# socket.net
KiCad netlist of a schematic drawn in EAGLE
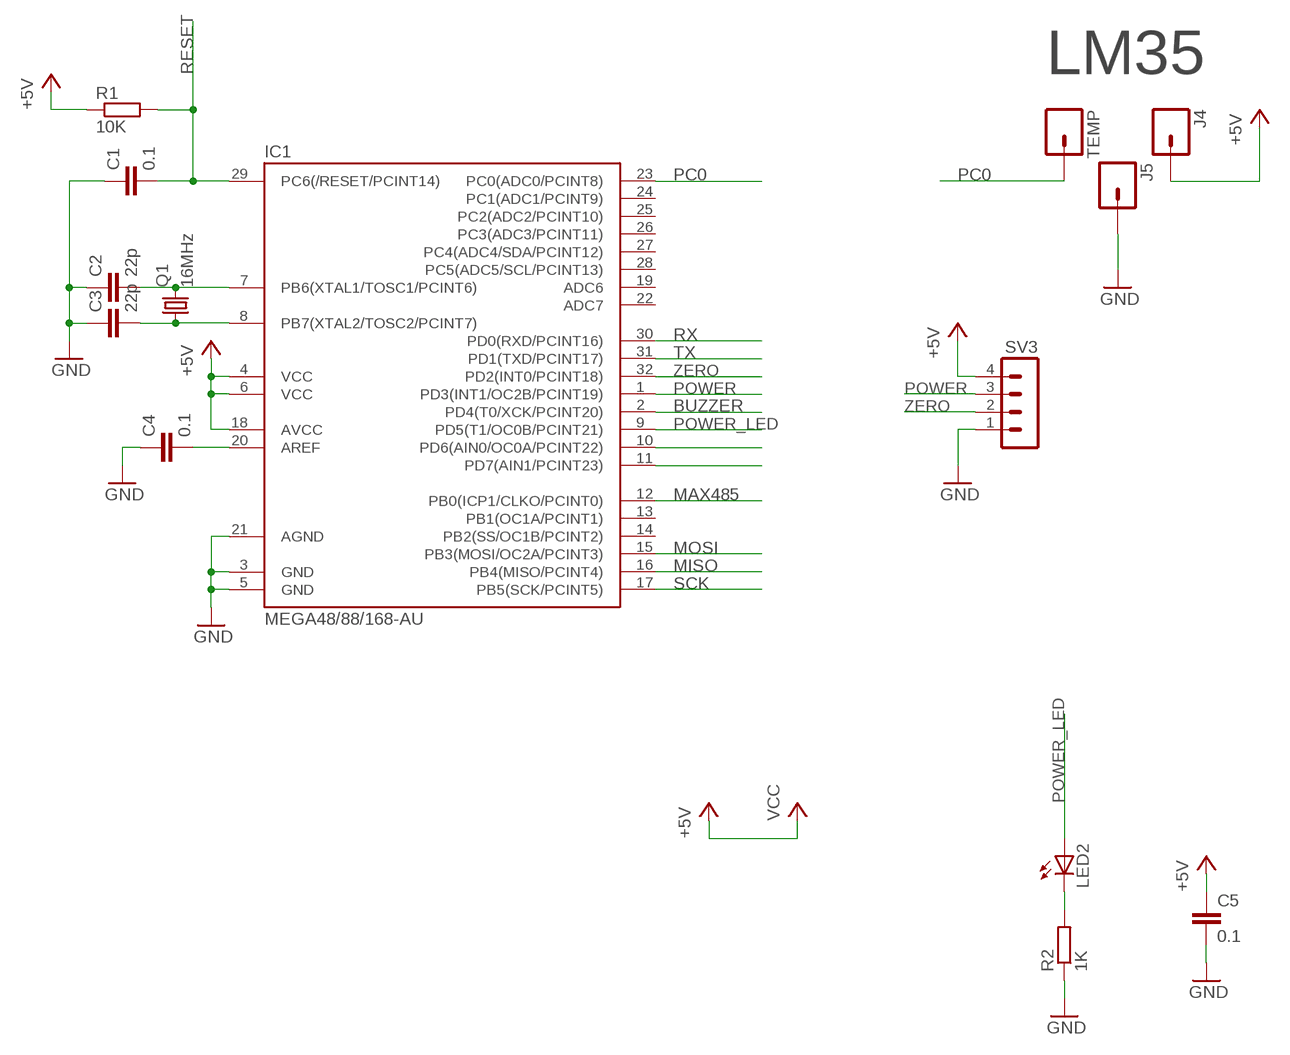
[diagram p0: schematic, sheet 1]
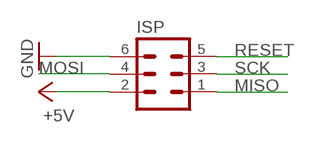
[diagram p1: schematic, sheet 2]
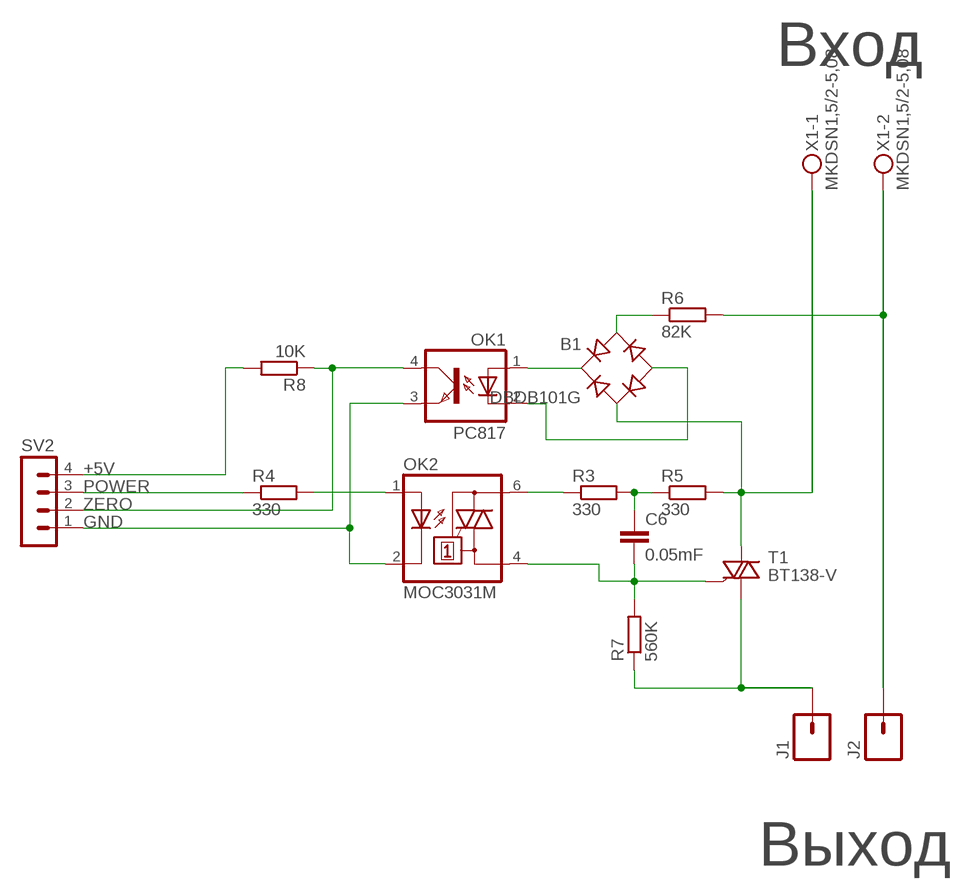
[diagram p2: schematic, sheet 3]
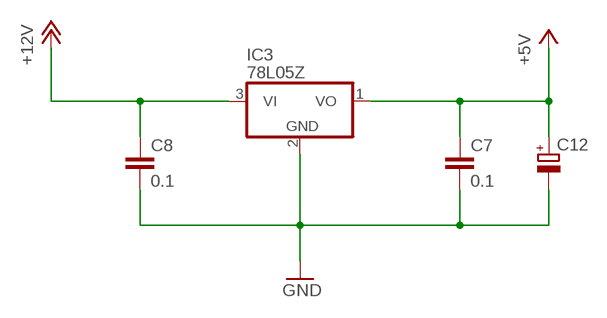
[diagram p3: schematic, sheet 4]
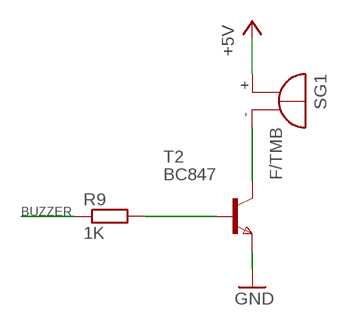
[diagram p4: schematic, sheet 5]
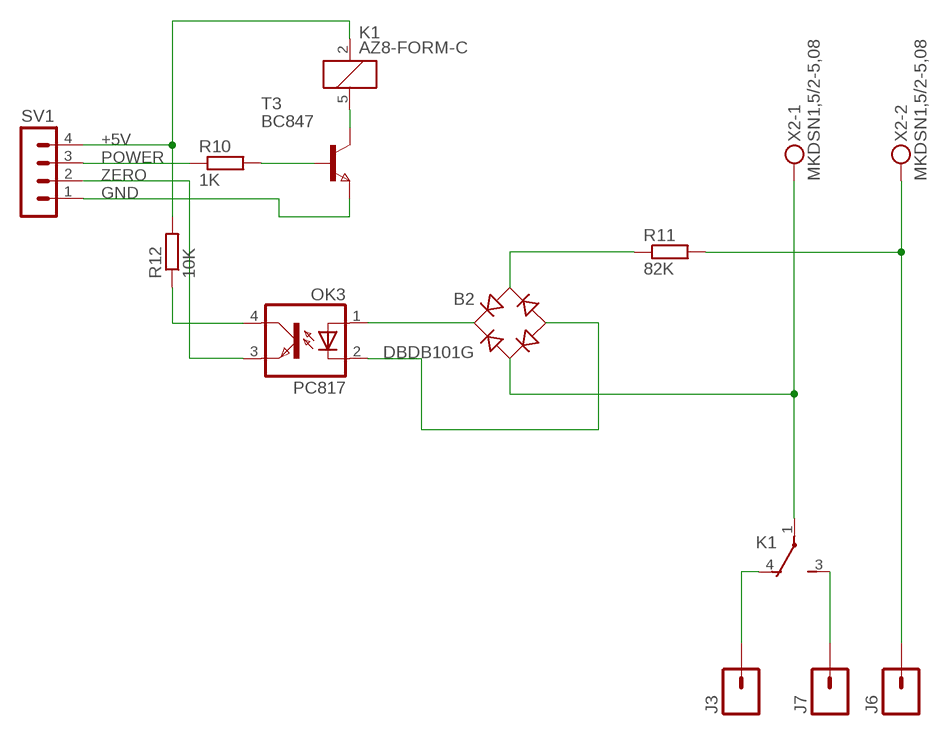
[diagram p5: schematic, sheet 6]
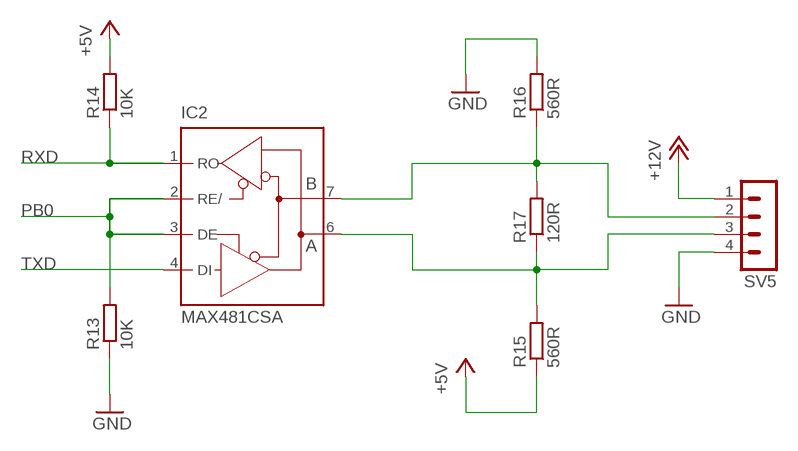
[diagram p6: schematic, sheet 7]

(export (version "E")
  (design (tool "Eeschema 10.0.6"))
  (components
    (comp (ref "B2")
      (value "DBDB101G")
      (footprint "eagle-import:DB")
      (libsource (lib "eagle-import") (part "DB?GDB101"))
    )
    (comp (ref "J3")
      (value "M01NOSILK-KIT")
      (footprint "eagle-import:1X01NS-KIT")
      (libsource (lib "eagle-import") (part "M01NOSILK-KIT"))
    )
    (comp (ref "J6")
      (value "M01NOSILK-KIT")
      (footprint "eagle-import:1X01NS-KIT")
      (libsource (lib "eagle-import") (part "M01NOSILK-KIT"))
    )
    (comp (ref "J7")
      (value "M01NOSILK-KIT")
      (footprint "eagle-import:1X01NS-KIT")
      (libsource (lib "eagle-import") (part "M01NOSILK-KIT"))
    )
    (comp (ref "K1")
      (value "AZ8-FORM-C")
      (footprint "eagle-import:AZ8")
      (libsource (lib "eagle-import") (part "AZ8-FORM-C"))
    )
    (comp (ref "OK3")
      (value "PC817")
      (footprint "eagle-import:DIL04")
      (fields (field (name "MPN") "PC817X4J000F"))
      (libsource (lib "eagle-import") (part "PC817"))
    )
    (comp (ref "R10")
      (value "1K")
      (footprint "eagle-import:M0805")
      (libsource (lib "eagle-import") (part "R-EU_M0805"))
    )
    (comp (ref "R11")
      (value "82K")
      (footprint "eagle-import:0309_10")
      (libsource (lib "eagle-import") (part "R-EU_0309/10"))
    )
    (comp (ref "R12")
      (value "10K")
      (footprint "eagle-import:M0805")
      (libsource (lib "eagle-import") (part "R-EU_M0805"))
    )
    (comp (ref "SV1")
      (value "MA04-1")
      (footprint "eagle-import:MA04-1")
      (libsource (lib "eagle-import") (part "MA04-1"))
    )
    (comp (ref "T3")
      (value "BC847")
      (footprint "eagle-import:SOT-23")
      (fields (field (name "MPN") "DSS20201L-7"))
      (libsource (lib "eagle-import") (part "NPNSOT23"))
    )
    (comp (ref "X2")
      (value "MKDSN1,5/2-5,08")
      (footprint "eagle-import:MKDSN1,5_2-5,08")
      (libsource (lib "eagle-import") (part "MKDSN1,5/2-5,08"))
    )
    (comp (ref "IC2")
      (value "MAX481CSA")
      (footprint "eagle-import:SO08")
      (fields (field (name "MF") "MAXIM"))
      (libsource (lib "eagle-import") (part "MAX481CSA"))
    )
    (comp (ref "R13")
      (value "10K")
      (footprint "eagle-import:R0805")
      (libsource (lib "eagle-import") (part "resistor_R-EU_R0805"))
    )
    (comp (ref "R14")
      (value "10K")
      (footprint "eagle-import:R0805")
      (libsource (lib "eagle-import") (part "resistor_R-EU_R0805"))
    )
    (comp (ref "R15")
      (value "560R")
      (footprint "eagle-import:R0805")
      (libsource (lib "eagle-import") (part "resistor_R-EU_R0805"))
    )
    (comp (ref "R16")
      (value "560R")
      (footprint "eagle-import:R0805")
      (libsource (lib "eagle-import") (part "resistor_R-EU_R0805"))
    )
    (comp (ref "R17")
      (value "120R")
      (footprint "eagle-import:R0805")
      (libsource (lib "eagle-import") (part "resistor_R-EU_R0805"))
    )
    (comp (ref "SV5")
      (value "MA04-1")
      (footprint "eagle-import:MA04-1")
      (libsource (lib "eagle-import") (part "MA04-1"))
    )
    (comp (ref "C7")
      (value "0.1")
      (footprint "eagle-import:C0805")
      (libsource (lib "eagle-import") (part "C-EUC0805"))
    )
    (comp (ref "C8")
      (value "0.1")
      (footprint "eagle-import:C0805")
      (libsource (lib "eagle-import") (part "C-EUC0805"))
    )
    (comp (ref "C12")
      (value "CPOL-EUE2,5-6E")
      (footprint "eagle-import:E2,5-6E")
      (libsource (lib "eagle-import") (part "CPOL-EUE2,5-6E"))
    )
    (comp (ref "IC3")
      (value "78L05Z")
      (footprint "eagle-import:TO92")
      (libsource (lib "eagle-import") (part "78ZL05"))
    )
    (comp (ref "B1")
      (value "DBDB101G")
      (footprint "eagle-import:DB")
      (libsource (lib "eagle-import") (part "DB?GDB101"))
    )
    (comp (ref "C6")
      (value "0.05mF")
      (footprint "eagle-import:C0805")
      (libsource (lib "eagle-import") (part "C-EUC0805"))
    )
    (comp (ref "J1")
      (value "M01NOSILK-KIT")
      (footprint "eagle-import:1X01NS-KIT")
      (libsource (lib "eagle-import") (part "M01NOSILK-KIT"))
    )
    (comp (ref "J2")
      (value "M01NOSILK-KIT")
      (footprint "eagle-import:1X01NS-KIT")
      (libsource (lib "eagle-import") (part "M01NOSILK-KIT"))
    )
    (comp (ref "OK1")
      (value "PC817")
      (footprint "eagle-import:DIL04")
      (fields (field (name "MPN") "PC817X4J000F"))
      (libsource (lib "eagle-import") (part "PC817"))
    )
    (comp (ref "OK2")
      (value "MOC3031M")
      (footprint "eagle-import:DIL06")
      (fields (field (name "MF") "FAIRCHILD SEMICONDUCTOR"))
      (libsource (lib "eagle-import") (part "MOC3031M"))
    )
    (comp (ref "R3")
      (value "330")
      (footprint "eagle-import:M0805")
      (libsource (lib "eagle-import") (part "R-EU_M0805"))
    )
    (comp (ref "R4")
      (value "330")
      (footprint "eagle-import:M0805")
      (libsource (lib "eagle-import") (part "R-EU_M0805"))
    )
    (comp (ref "R5")
      (value "330")
      (footprint "eagle-import:M0805")
      (libsource (lib "eagle-import") (part "R-EU_M0805"))
    )
    (comp (ref "R6")
      (value "82K")
      (footprint "eagle-import:0309_10")
      (libsource (lib "eagle-import") (part "R-EU_0309/10"))
    )
    (comp (ref "R7")
      (value "560K")
      (footprint "eagle-import:M0805")
      (libsource (lib "eagle-import") (part "R-EU_M0805"))
    )
    (comp (ref "R8")
      (value "10K")
      (footprint "eagle-import:M0805")
      (libsource (lib "eagle-import") (part "R-EU_M0805"))
    )
    (comp (ref "SV2")
      (value "MA04-1")
      (footprint "eagle-import:MA04-1")
      (libsource (lib "eagle-import") (part "MA04-1"))
    )
    (comp (ref "T1")
      (value "BT138-V")
      (footprint "eagle-import:TO220BV")
      (libsource (lib "eagle-import") (part "BT138-V"))
    )
    (comp (ref "X1")
      (value "MKDSN1,5/2-5,08")
      (footprint "eagle-import:MKDSN1,5_2-5,08")
      (libsource (lib "eagle-import") (part "MKDSN1,5/2-5,08"))
    )
    (comp (ref "C1")
      (value "0.1")
      (footprint "eagle-import:C0805")
      (libsource (lib "eagle-import") (part "C-EUC0805"))
    )
    (comp (ref "C2")
      (value "22p")
      (footprint "eagle-import:C0805")
      (libsource (lib "eagle-import") (part "C-EUC0805"))
    )
    (comp (ref "C3")
      (value "22p")
      (footprint "eagle-import:C0805")
      (libsource (lib "eagle-import") (part "C-EUC0805"))
    )
    (comp (ref "C4")
      (value "0.1")
      (footprint "eagle-import:C0805")
      (libsource (lib "eagle-import") (part "C-EUC0805"))
    )
    (comp (ref "C5")
      (value "0.1")
      (footprint "eagle-import:C0805")
      (libsource (lib "eagle-import") (part "C-EUC0805"))
    )
    (comp (ref "IC1")
      (value "MEGA48/88/168-AU")
      (footprint "eagle-import:TQFP32-08")
      (libsource (lib "eagle-import") (part "MEGA48/88/168-AU"))
    )
    (comp (ref "J4")
      (value "M01PTH_NO_SILK_YES_STOP")
      (footprint "eagle-import:1X01_NO_SILK")
      (libsource (lib "eagle-import") (part "M01PTH_NO_SILK_YES_STOP"))
    )
    (comp (ref "J5")
      (value "M01PTH_NO_SILK_YES_STOP")
      (footprint "eagle-import:1X01_NO_SILK")
      (libsource (lib "eagle-import") (part "M01PTH_NO_SILK_YES_STOP"))
    )
    (comp (ref "LED2")
      (value "LEDCHIPLED_0805")
      (footprint "eagle-import:CHIPLED_0805")
      (libsource (lib "eagle-import") (part "LEDCHIPLED_0805"))
    )
    (comp (ref "Q1")
      (value "16MHz")
      (footprint "eagle-import:HC49U70")
      (libsource (lib "eagle-import") (part "CRYSTALHC49U70"))
    )
    (comp (ref "R1")
      (value "10K")
      (footprint "eagle-import:R0805")
      (libsource (lib "eagle-import") (part "R-EU_R0805"))
    )
    (comp (ref "R2")
      (value "1K")
      (footprint "eagle-import:R0805")
      (libsource (lib "eagle-import") (part "R-EU_R0805"))
    )
    (comp (ref "SV3")
      (value "MA04-1")
      (footprint "eagle-import:MA04-1")
      (libsource (lib "eagle-import") (part "MA04-1"))
    )
    (comp (ref "TEMP")
      (value "M01PTH_NO_SILK_YES_STOP")
      (footprint "eagle-import:1X01_NO_SILK")
      (libsource (lib "eagle-import") (part "M01PTH_NO_SILK_YES_STOP"))
    )
    (comp (ref "R9")
      (value "1K")
      (footprint "eagle-import:M1206")
      (libsource (lib "eagle-import") (part "R-EU_M1206"))
    )
    (comp (ref "SG1")
      (value "F/TMB")
      (footprint "eagle-import:F_TMB")
      (libsource (lib "eagle-import") (part "F/TMB"))
    )
    (comp (ref "T2")
      (value "BC847")
      (footprint "eagle-import:SOT-23")
      (fields (field (name "MPN") "DSS20201L-7"))
      (libsource (lib "eagle-import") (part "NPNSOT23"))
    )
    (comp (ref "ISP")
      (value "MA03-2")
      (footprint "eagle-import:MA03-2")
      (libsource (lib "eagle-import") (part "MA03-2"))
    )
  )
  (nets
    (net (code "1") (name "+5V") (class "Default")
      (node (ref "C12") (pin "+") (pinfunction "+_+") (pintype "passive"))
      (node (ref "C5") (pin "1") (pinfunction "1_1") (pintype "passive"))
      (node (ref "C7") (pin "1") (pinfunction "1_1") (pintype "passive"))
      (node (ref "IC1") (pin "18") (pinfunction "AVCC_18") (pintype "passive"))
      (node (ref "IC1") (pin "4") (pinfunction "VCC_4") (pintype "power_in"))
      (node (ref "IC1") (pin "6") (pinfunction "VCC_6") (pintype "power_in"))
      (node (ref "IC3") (pin "1") (pinfunction "VO_1") (pintype "passive"))
      (node (ref "ISP") (pin "2") (pinfunction "2_2") (pintype "passive"))
      (node (ref "J4") (pin "1") (pinfunction "1_1") (pintype "passive"))
      (node (ref "R1") (pin "1") (pinfunction "1_1") (pintype "passive"))
      (node (ref "R14") (pin "2") (pinfunction "2_2") (pintype "passive"))
      (node (ref "R15") (pin "1") (pinfunction "1_1") (pintype "passive"))
      (node (ref "SG1") (pin "+") (pinfunction "+_+") (pintype "passive"))
      (node (ref "SV3") (pin "4") (pinfunction "4_4") (pintype "passive"))
    )
    (net (code "2") (name "+12V") (class "Default")
      (node (ref "C8") (pin "1") (pinfunction "1_1") (pintype "passive"))
      (node (ref "IC3") (pin "3") (pinfunction "VI_3") (pintype "input"))
      (node (ref "SV5") (pin "1") (pinfunction "1_1") (pintype "passive"))
    )
    (net (code "3") (name "BUZZER") (class "Default")
      (node (ref "IC1") (pin "2") (pinfunction "PD4(T0/XCK/PCINT20)_2") (pintype "bidirectional"))
      (node (ref "R9") (pin "1") (pinfunction "1_1") (pintype "passive"))
    )
    (net (code "4") (name "GND") (class "Default")
      (node (ref "C1") (pin "1") (pinfunction "1_1") (pintype "passive"))
      (node (ref "C12") (pin "-") (pinfunction "-_-") (pintype "passive"))
      (node (ref "C2") (pin "1") (pinfunction "1_1") (pintype "passive"))
      (node (ref "C3") (pin "1") (pinfunction "1_1") (pintype "passive"))
      (node (ref "C4") (pin "1") (pinfunction "1_1") (pintype "passive"))
      (node (ref "C5") (pin "2") (pinfunction "2_2") (pintype "passive"))
      (node (ref "C7") (pin "2") (pinfunction "2_2") (pintype "passive"))
      (node (ref "C8") (pin "2") (pinfunction "2_2") (pintype "passive"))
      (node (ref "IC1") (pin "21") (pinfunction "AGND_21") (pintype "power_in"))
      (node (ref "IC1") (pin "3") (pinfunction "GND_3") (pintype "power_in"))
      (node (ref "IC1") (pin "5") (pinfunction "GND_5") (pintype "power_in"))
      (node (ref "IC3") (pin "2") (pinfunction "GND_2") (pintype "passive"))
      (node (ref "ISP") (pin "6") (pinfunction "6_6") (pintype "passive"))
      (node (ref "J5") (pin "1") (pinfunction "1_1") (pintype "passive"))
      (node (ref "R13") (pin "1") (pinfunction "1_1") (pintype "passive"))
      (node (ref "R16") (pin "2") (pinfunction "2_2") (pintype "passive"))
      (node (ref "R2") (pin "1") (pinfunction "1_1") (pintype "passive"))
      (node (ref "SV3") (pin "1") (pinfunction "1_1") (pintype "passive"))
      (node (ref "SV5") (pin "4") (pinfunction "4_4") (pintype "passive"))
      (node (ref "T2") (pin "2") (pinfunction "E_2") (pintype "passive"))
    )
    (net (code "5") (name "MISO") (class "Default")
      (node (ref "IC1") (pin "16") (pinfunction "PB4(MISO/PCINT4)_16") (pintype "bidirectional"))
      (node (ref "ISP") (pin "1") (pinfunction "1_1") (pintype "passive"))
    )
    (net (code "6") (name "MOSI") (class "Default")
      (node (ref "IC1") (pin "15") (pinfunction "PB3(MOSI/OC2A/PCINT3)_15") (pintype "bidirectional"))
      (node (ref "ISP") (pin "4") (pinfunction "4_4") (pintype "passive"))
    )
    (net (code "7") (name "Net-(B1-PadAC1)") (class "Default")
      (node (ref "B1") (pin "AC1") (pinfunction "AC1_AC1") (pintype "passive"))
      (node (ref "R6") (pin "1") (pinfunction "1_1") (pintype "passive"))
    )
    (net (code "8") (name "Net-(B2-PadAC1)") (class "Default")
      (node (ref "B2") (pin "AC1") (pinfunction "AC1_AC1") (pintype "passive"))
      (node (ref "R11") (pin "1") (pinfunction "1_1") (pintype "passive"))
    )
    (net (code "9") (name "Net-(C6-Pad1)") (class "Default")
      (node (ref "C6") (pin "1") (pinfunction "1_1") (pintype "passive"))
      (node (ref "R3") (pin "2") (pinfunction "2_2") (pintype "passive"))
      (node (ref "R5") (pin "1") (pinfunction "1_1") (pintype "passive"))
    )
    (net (code "10") (name "Net-(IC1-AREF)") (class "Default")
      (node (ref "C4") (pin "2") (pinfunction "2_2") (pintype "passive"))
      (node (ref "IC1") (pin "20") (pinfunction "AREF_20") (pintype "passive"))
    )
    (net (code "11") (name "Net-(IC1-PB6(XTAL1{slash}TOSC1{slash}PCINT6))") (class "Default")
      (node (ref "C2") (pin "2") (pinfunction "2_2") (pintype "passive"))
      (node (ref "IC1") (pin "7") (pinfunction "PB6(XTAL1/TOSC1/PCINT6)_7") (pintype "bidirectional"))
      (node (ref "Q1") (pin "2") (pinfunction "2_2") (pintype "passive"))
    )
    (net (code "12") (name "Net-(IC1-PB7(XTAL2{slash}TOSC2{slash}PCINT7))") (class "Default")
      (node (ref "C3") (pin "2") (pinfunction "2_2") (pintype "passive"))
      (node (ref "IC1") (pin "8") (pinfunction "PB7(XTAL2/TOSC2/PCINT7)_8") (pintype "bidirectional"))
      (node (ref "Q1") (pin "1") (pinfunction "1_1") (pintype "passive"))
    )
    (net (code "13") (name "Net-(IC2A-A)") (class "Default")
      (node (ref "IC2") (pin "6") (pinfunction "A_6") (pintype "passive"))
      (node (ref "R15") (pin "2") (pinfunction "2_2") (pintype "passive"))
      (node (ref "R17") (pin "1") (pinfunction "1_1") (pintype "passive"))
      (node (ref "SV5") (pin "3") (pinfunction "3_3") (pintype "passive"))
    )
    (net (code "14") (name "Net-(IC2A-B)") (class "Default")
      (node (ref "IC2") (pin "7") (pinfunction "B_7") (pintype "passive"))
      (node (ref "R16") (pin "1") (pinfunction "1_1") (pintype "passive"))
      (node (ref "R17") (pin "2") (pinfunction "2_2") (pintype "passive"))
      (node (ref "SV5") (pin "2") (pinfunction "2_2") (pintype "passive"))
    )
    (net (code "15") (name "Net-(K1A-O)") (class "Default")
      (node (ref "J3") (pin "1") (pinfunction "1_1") (pintype "passive"))
      (node (ref "K1") (pin "4") (pinfunction "O_4") (pintype "passive"))
    )
    (net (code "16") (name "Net-(K1A-P)") (class "Default")
      (node (ref "B2") (pin "AC2") (pinfunction "AC2_AC2") (pintype "passive"))
      (node (ref "K1") (pin "1") (pinfunction "P_1") (pintype "passive"))
      (node (ref "X2") (pin "1") (pinfunction "KL_1") (pintype "passive"))
    )
    (net (code "17") (name "Net-(K1A-S)") (class "Default")
      (node (ref "J7") (pin "1") (pinfunction "1_1") (pintype "passive"))
      (node (ref "K1") (pin "3") (pinfunction "S_3") (pintype "passive"))
    )
    (net (code "18") (name "Net-(K1B-1)") (class "Default")
      (node (ref "K1") (pin "2") (pinfunction "1_2") (pintype "passive"))
      (node (ref "R12") (pin "2") (pinfunction "2_2") (pintype "passive"))
      (node (ref "SV1") (pin "4") (pinfunction "4_4") (pintype "passive"))
    )
    (net (code "19") (name "Net-(K1B-2)") (class "Default")
      (node (ref "K1") (pin "5") (pinfunction "2_5") (pintype "passive"))
      (node (ref "T3") (pin "1") (pinfunction "C_1") (pintype "passive"))
    )
    (net (code "20") (name "Net-(LED2-PadC)") (class "Default")
      (node (ref "LED2") (pin "C") (pinfunction "C_C") (pintype "passive"))
      (node (ref "R2") (pin "2") (pinfunction "2_2") (pintype "passive"))
    )
    (net (code "21") (name "Net-(OK1-A)") (class "Default")
      (node (ref "B1") (pin "+") (pinfunction "+_+") (pintype "passive"))
      (node (ref "OK1") (pin "1") (pinfunction "A_1") (pintype "passive"))
    )
    (net (code "22") (name "Net-(OK1-C)") (class "Default")
      (node (ref "B1") (pin "-") (pinfunction "-_-") (pintype "passive"))
      (node (ref "OK1") (pin "2") (pinfunction "C_2") (pintype "passive"))
    )
    (net (code "23") (name "Net-(OK1-COL)") (class "Default")
      (node (ref "OK1") (pin "4") (pinfunction "COL_4") (pintype "passive"))
      (node (ref "R8") (pin "1") (pinfunction "1_1") (pintype "passive"))
      (node (ref "SV2") (pin "2") (pinfunction "2_2") (pintype "passive"))
    )
    (net (code "24") (name "Net-(OK1-EMIT)") (class "Default")
      (node (ref "OK1") (pin "3") (pinfunction "EMIT_3") (pintype "passive"))
      (node (ref "OK2") (pin "2") (pinfunction "C_2") (pintype "passive"))
      (node (ref "SV2") (pin "1") (pinfunction "1_1") (pintype "passive"))
    )
    (net (code "25") (name "Net-(OK2-A)") (class "Default")
      (node (ref "OK2") (pin "1") (pinfunction "A_1") (pintype "passive"))
      (node (ref "R4") (pin "2") (pinfunction "2_2") (pintype "passive"))
    )
    (net (code "26") (name "Net-(OK2-A1)") (class "Default")
      (node (ref "C6") (pin "2") (pinfunction "2_2") (pintype "passive"))
      (node (ref "OK2") (pin "4") (pinfunction "A1_4") (pintype "passive"))
      (node (ref "R7") (pin "2") (pinfunction "2_2") (pintype "passive"))
      (node (ref "T1") (pin "G") (pinfunction "G_G") (pintype "passive"))
    )
    (net (code "27") (name "Net-(OK2-A2)") (class "Default")
      (node (ref "OK2") (pin "6") (pinfunction "A2_6") (pintype "passive"))
      (node (ref "R3") (pin "1") (pinfunction "1_1") (pintype "passive"))
    )
    (net (code "28") (name "Net-(OK3-A)") (class "Default")
      (node (ref "B2") (pin "+") (pinfunction "+_+") (pintype "passive"))
      (node (ref "OK3") (pin "1") (pinfunction "A_1") (pintype "passive"))
    )
    (net (code "29") (name "Net-(OK3-C)") (class "Default")
      (node (ref "B2") (pin "-") (pinfunction "-_-") (pintype "passive"))
      (node (ref "OK3") (pin "2") (pinfunction "C_2") (pintype "passive"))
    )
    (net (code "30") (name "Net-(OK3-COL)") (class "Default")
      (node (ref "OK3") (pin "4") (pinfunction "COL_4") (pintype "passive"))
      (node (ref "R12") (pin "1") (pinfunction "1_1") (pintype "passive"))
    )
    (net (code "31") (name "Net-(OK3-EMIT)") (class "Default")
      (node (ref "OK3") (pin "3") (pinfunction "EMIT_3") (pintype "passive"))
      (node (ref "SV1") (pin "2") (pinfunction "2_2") (pintype "passive"))
    )
    (net (code "32") (name "Net-(R4-Pad1)") (class "Default")
      (node (ref "R4") (pin "1") (pinfunction "1_1") (pintype "passive"))
      (node (ref "SV2") (pin "3") (pinfunction "3_3") (pintype "passive"))
    )
    (net (code "33") (name "Net-(R8-Pad2)") (class "Default")
      (node (ref "R8") (pin "2") (pinfunction "2_2") (pintype "passive"))
      (node (ref "SV2") (pin "4") (pinfunction "4_4") (pintype "passive"))
    )
    (net (code "34") (name "Net-(R10-Pad1)") (class "Default")
      (node (ref "R10") (pin "1") (pinfunction "1_1") (pintype "passive"))
      (node (ref "SV1") (pin "3") (pinfunction "3_3") (pintype "passive"))
    )
    (net (code "35") (name "Net-(T1-A1)") (class "Default")
      (node (ref "J1") (pin "1") (pinfunction "1_1") (pintype "passive"))
      (node (ref "R7") (pin "1") (pinfunction "1_1") (pintype "passive"))
      (node (ref "T1") (pin "T1") (pinfunction "A1_T1") (pintype "passive"))
    )
    (net (code "36") (name "Net-(T1-A2)") (class "Default")
      (node (ref "B1") (pin "AC2") (pinfunction "AC2_AC2") (pintype "passive"))
      (node (ref "R5") (pin "2") (pinfunction "2_2") (pintype "passive"))
      (node (ref "T1") (pin "T2") (pinfunction "A2_T2") (pintype "passive"))
      (node (ref "X1") (pin "1") (pinfunction "KL_1") (pintype "passive"))
    )
    (net (code "37") (name "Net-(T2-B)") (class "Default")
      (node (ref "R9") (pin "2") (pinfunction "2_2") (pintype "passive"))
      (node (ref "T2") (pin "3") (pinfunction "B_3") (pintype "passive"))
    )
    (net (code "38") (name "Net-(T2-C)") (class "Default")
      (node (ref "SG1") (pin "-") (pinfunction "-_-") (pintype "passive"))
      (node (ref "T2") (pin "1") (pinfunction "C_1") (pintype "passive"))
    )
    (net (code "39") (name "Net-(T3-B)") (class "Default")
      (node (ref "R10") (pin "2") (pinfunction "2_2") (pintype "passive"))
      (node (ref "T3") (pin "3") (pinfunction "B_3") (pintype "passive"))
    )
    (net (code "40") (name "Net-(T3-E)") (class "Default")
      (node (ref "SV1") (pin "1") (pinfunction "1_1") (pintype "passive"))
      (node (ref "T3") (pin "2") (pinfunction "E_2") (pintype "passive"))
    )
    (net (code "41") (name "Net-(X1B-KL)") (class "Default")
      (node (ref "J2") (pin "1") (pinfunction "1_1") (pintype "passive"))
      (node (ref "R6") (pin "2") (pinfunction "2_2") (pintype "passive"))
      (node (ref "X1") (pin "2") (pinfunction "KL_2") (pintype "passive"))
    )
    (net (code "42") (name "Net-(X2B-KL)") (class "Default")
      (node (ref "J6") (pin "1") (pinfunction "1_1") (pintype "passive"))
      (node (ref "R11") (pin "2") (pinfunction "2_2") (pintype "passive"))
      (node (ref "X2") (pin "2") (pinfunction "KL_2") (pintype "passive"))
    )
    (net (code "43") (name "PB0") (class "Default")
      (node (ref "IC1") (pin "12") (pinfunction "PB0(ICP1/CLKO/PCINT0)_12") (pintype "bidirectional"))
      (node (ref "IC2") (pin "2") (pinfunction "RE/_2") (pintype "input"))
      (node (ref "IC2") (pin "3") (pinfunction "DE_3") (pintype "input"))
      (node (ref "R13") (pin "2") (pinfunction "2_2") (pintype "passive"))
    )
    (net (code "44") (name "PC0") (class "Default")
      (node (ref "IC1") (pin "23") (pinfunction "PC0(ADC0/PCINT8)_23") (pintype "bidirectional"))
      (node (ref "TEMP") (pin "1") (pinfunction "1_1") (pintype "passive"))
    )
    (net (code "45") (name "PD3") (class "Default")
      (node (ref "IC1") (pin "1") (pinfunction "PD3(INT1/OC2B/PCINT19)_1") (pintype "bidirectional"))
      (node (ref "SV3") (pin "3") (pinfunction "3_3") (pintype "passive"))
    )
    (net (code "46") (name "PD4") (class "Default")
      (node (ref "IC1") (pin "32") (pinfunction "PD2(INT0/PCINT18)_32") (pintype "bidirectional"))
      (node (ref "SV3") (pin "2") (pinfunction "2_2") (pintype "passive"))
    )
    (net (code "47") (name "POWER_LED") (class "Default")
      (node (ref "IC1") (pin "9") (pinfunction "PD5(T1/OC0B/PCINT21)_9") (pintype "bidirectional"))
      (node (ref "LED2") (pin "A") (pinfunction "A_A") (pintype "passive"))
    )
    (net (code "48") (name "RESET") (class "Default")
      (node (ref "C1") (pin "2") (pinfunction "2_2") (pintype "passive"))
      (node (ref "IC1") (pin "29") (pinfunction "PC6(/RESET/PCINT14)_29") (pintype "bidirectional"))
      (node (ref "ISP") (pin "5") (pinfunction "5_5") (pintype "passive"))
      (node (ref "R1") (pin "2") (pinfunction "2_2") (pintype "passive"))
    )
    (net (code "49") (name "RX") (class "Default")
      (node (ref "IC1") (pin "30") (pinfunction "PD0(RXD/PCINT16)_30") (pintype "bidirectional"))
      (node (ref "IC2") (pin "1") (pinfunction "RO_1") (pintype "output"))
      (node (ref "R14") (pin "1") (pinfunction "1_1") (pintype "passive"))
    )
    (net (code "50") (name "SCK") (class "Default")
      (node (ref "IC1") (pin "17") (pinfunction "PB5(SCK/PCINT5)_17") (pintype "bidirectional"))
      (node (ref "ISP") (pin "3") (pinfunction "3_3") (pintype "passive"))
    )
    (net (code "51") (name "TX") (class "Default")
      (node (ref "IC1") (pin "31") (pinfunction "PD1(TXD/PCINT17)_31") (pintype "bidirectional"))
      (node (ref "IC2") (pin "4") (pinfunction "DI_4") (pintype "input"))
    )
    (net (code "52") (name "unconnected-(IC1-ADC6-Pad19)") (class "Default")
      (node (ref "IC1") (pin "19") (pinfunction "ADC6_19") (pintype "passive"))
    )
    (net (code "53") (name "unconnected-(IC1-ADC7-Pad22)") (class "Default")
      (node (ref "IC1") (pin "22") (pinfunction "ADC7_22") (pintype "passive"))
    )
    (net (code "54") (name "unconnected-(IC1-PB1(OC1A{slash}PCINT1)-Pad13)") (class "Default")
      (node (ref "IC1") (pin "13") (pinfunction "PB1(OC1A/PCINT1)_13") (pintype "bidirectional"))
    )
    (net (code "55") (name "unconnected-(IC1-PB2(SS{slash}OC1B{slash}PCINT2)-Pad14)") (class "Default")
      (node (ref "IC1") (pin "14") (pinfunction "PB2(SS/OC1B/PCINT2)_14") (pintype "bidirectional"))
    )
    (net (code "56") (name "unconnected-(IC1-PC1(ADC1{slash}PCINT9)-Pad24)") (class "Default")
      (node (ref "IC1") (pin "24") (pinfunction "PC1(ADC1/PCINT9)_24") (pintype "bidirectional"))
    )
    (net (code "57") (name "unconnected-(IC1-PC2(ADC2{slash}PCINT10)-Pad25)") (class "Default")
      (node (ref "IC1") (pin "25") (pinfunction "PC2(ADC2/PCINT10)_25") (pintype "bidirectional"))
    )
    (net (code "58") (name "unconnected-(IC1-PC3(ADC3{slash}PCINT11)-Pad26)") (class "Default")
      (node (ref "IC1") (pin "26") (pinfunction "PC3(ADC3/PCINT11)_26") (pintype "bidirectional"))
    )
    (net (code "59") (name "unconnected-(IC1-PC4(ADC4{slash}SDA{slash}PCINT12)-Pad27)") (class "Default")
      (node (ref "IC1") (pin "27") (pinfunction "PC4(ADC4/SDA/PCINT12)_27") (pintype "bidirectional"))
    )
    (net (code "60") (name "unconnected-(IC1-PC5(ADC5{slash}SCL{slash}PCINT13)-Pad28)") (class "Default")
      (node (ref "IC1") (pin "28") (pinfunction "PC5(ADC5/SCL/PCINT13)_28") (pintype "bidirectional"))
    )
    (net (code "61") (name "unconnected-(IC1-PD6(AIN0{slash}OC0A{slash}PCINT22)-Pad10)") (class "Default")
      (node (ref "IC1") (pin "10") (pinfunction "PD6(AIN0/OC0A/PCINT22)_10") (pintype "bidirectional"))
    )
    (net (code "62") (name "unconnected-(IC1-PD7(AIN1{slash}PCINT23)-Pad11)") (class "Default")
      (node (ref "IC1") (pin "11") (pinfunction "PD7(AIN1/PCINT23)_11") (pintype "bidirectional"))
    )
  )
)
